# LDO_Pos.net
KiCad netlist of a schematic drawn in Altium Designer
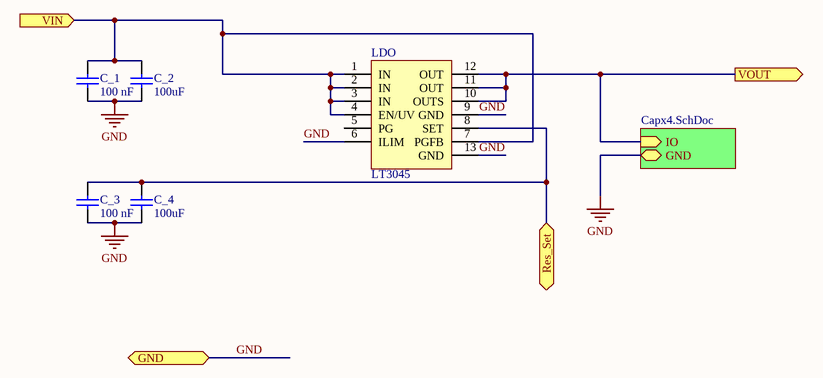
[diagram p0: LDO_Pos.SchDoc]

(export (version "E")
  (design (tool "Eeschema 10.0.6"))
  (components
    (comp (ref "C_1")
      (value "100 nF")
      (footprint "MRI_ADC:KEMET C0805C104J8RACTU")
      (description "CAP CER 0.1UF 10V X7R 0805\r\n±10% 10V Ceramic Capacitor X7R 0805 (2012 Metric)")
      (fields (field (name "Comment") "Cap 100nF 0805"))
      (libsource (lib "MRI_ADC") (part "Cap 100nF 0805"))
    )
    (comp (ref "C_2")
      (value "100uF")
      (footprint "MRI_ADC:Taiyo Yuden JMK316ABJ107ML-T")
      (description "CAP CER 100UF 6.3V X5R 1206\r\n±20% 6.3V Ceramic Capacitor X5R 1206 (3216 Metric)")
      (fields (field (name "Comment") "Cap 100uF 1206") (field (name "PUBLISHER") "Altium Limited"))
      (libsource (lib "MRI_ADC") (part "Cap 100uF 1206"))
    )
    (comp (ref "C_3")
      (value "100 nF")
      (footprint "MRI_ADC:KEMET C0805C104J8RACTU")
      (description "CAP CER 0.1UF 10V X7R 0805\r\n±10% 10V Ceramic Capacitor X7R 0805 (2012 Metric)")
      (fields (field (name "Comment") "Cap 100nF 0805"))
      (libsource (lib "MRI_ADC") (part "Cap 100nF 0805"))
    )
    (comp (ref "C_4")
      (value "100uF")
      (footprint "MRI_ADC:Taiyo Yuden JMK316ABJ107ML-T")
      (description "CAP CER 100UF 6.3V X5R 1206\r\n±20% 6.3V Ceramic Capacitor X5R 1206 (3216 Metric)")
      (fields (field (name "Comment") "Cap 100uF 1206") (field (name "PUBLISHER") "Altium Limited"))
      (libsource (lib "MRI_ADC") (part "Cap 100uF 1206"))
    )
    (comp (ref "LDO")
      (value "LT3045")
      (footprint "MRI_ADC:ADI LT3045IMSE#PBF")
      (description "IC REG LINEAR 0V 500MA 12MSOP\r\nLinear Voltage Regulator IC Output 500mA 12-MSOP-EP")
      (libsource (lib "MRI_ADC") (part "LT3045"))
    )
  )
  (nets
    (net (code "1") (name "/Res_Set") (class "Default")
      (node (ref "C_3") (pin "1") (pinfunction "1_1") (pintype "passive"))
      (node (ref "C_4") (pin "1") (pinfunction "1_1") (pintype "passive"))
      (node (ref "LDO") (pin "8") (pinfunction "SET_8") (pintype "passive"))
    )
    (net (code "2") (name "/VIN") (class "Default")
      (node (ref "C_1") (pin "1") (pinfunction "1_1") (pintype "passive"))
      (node (ref "C_2") (pin "1") (pinfunction "1_1") (pintype "passive"))
      (node (ref "LDO") (pin "1") (pinfunction "IN_1") (pintype "passive"))
      (node (ref "LDO") (pin "2") (pinfunction "IN_2") (pintype "passive"))
      (node (ref "LDO") (pin "3") (pinfunction "IN_3") (pintype "passive"))
      (node (ref "LDO") (pin "4") (pinfunction "EN/UV_4") (pintype "passive"))
      (node (ref "LDO") (pin "7") (pinfunction "PGFB_7") (pintype "passive"))
    )
    (net (code "3") (name "/VOUT") (class "Default")
      (node (ref "LDO") (pin "10") (pinfunction "OUTS_10") (pintype "passive"))
      (node (ref "LDO") (pin "11") (pinfunction "OUT_11") (pintype "passive"))
      (node (ref "LDO") (pin "12") (pinfunction "OUT_12") (pintype "passive"))
    )
    (net (code "4") (name "GND") (class "Default")
      (node (ref "C_1") (pin "2") (pinfunction "2_2") (pintype "passive"))
      (node (ref "C_2") (pin "2") (pinfunction "2_2") (pintype "passive"))
      (node (ref "C_3") (pin "2") (pinfunction "2_2") (pintype "passive"))
      (node (ref "C_4") (pin "2") (pinfunction "2_2") (pintype "passive"))
      (node (ref "LDO") (pin "13") (pinfunction "GND_13") (pintype "passive"))
      (node (ref "LDO") (pin "6") (pinfunction "ILIM_6") (pintype "passive"))
      (node (ref "LDO") (pin "9") (pinfunction "GND_9") (pintype "passive"))
    )
    (net (code "5") (name "unconnected-(LDO-PG-Pad5)") (class "Default")
      (node (ref "LDO") (pin "5") (pinfunction "PG_5") (pintype "passive"))
    )
  )
)
